# pcb-breakout-bt111.net
KiCad netlist of a schematic drawn in EAGLE
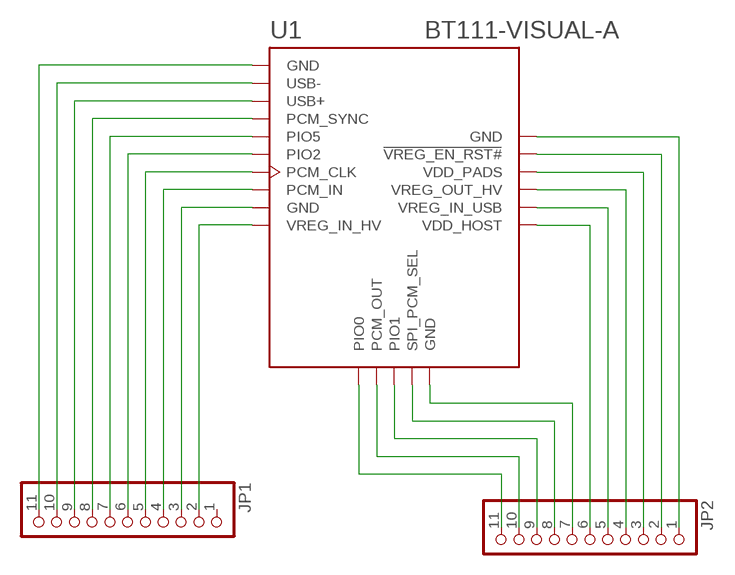
[diagram p0: schematic, sheet 1]

(export (version "E")
  (design (tool "Eeschema 10.0.6"))
  (components
    (comp (ref "JP1")
      (value "PINHD-1X11")
      (footprint "eagle-import:1X11")
      (libsource (lib "eagle-import") (part "PINHD-1X11"))
    )
    (comp (ref "JP2")
      (value "PINHD-1X11")
      (footprint "eagle-import:1X11")
      (libsource (lib "eagle-import") (part "PINHD-1X11"))
    )
    (comp (ref "U1")
      (value "BT111-VISUAL-A")
      (footprint "eagle-import:BT111-A")
      (libsource (lib "eagle-import") (part "BT111-VISUAL-A"))
    )
  )
  (nets
    (net (code "1") (name "Net-(JP1-Pad2)") (class "Default")
      (node (ref "JP1") (pin "2") (pinfunction "2_2") (pintype "passive"))
      (node (ref "U1") (pin "VREG_IN_HV") (pinfunction "VREG_IN_HV_VREG_IN_HV") (pintype "power_in"))
    )
    (net (code "2") (name "Net-(JP1-Pad3)") (class "Default")
      (node (ref "JP1") (pin "3") (pinfunction "3_3") (pintype "passive"))
      (node (ref "U1") (pin "GND@2") (pinfunction "GND_GND@2") (pintype "power_in"))
    )
    (net (code "3") (name "Net-(JP1-Pad4)") (class "Default")
      (node (ref "JP1") (pin "4") (pinfunction "4_4") (pintype "passive"))
      (node (ref "U1") (pin "PCM_IN") (pinfunction "PCM_IN_PCM_IN") (pintype "input"))
    )
    (net (code "4") (name "Net-(JP1-Pad5)") (class "Default")
      (node (ref "JP1") (pin "5") (pinfunction "5_5") (pintype "passive"))
      (node (ref "U1") (pin "PCM_CLK") (pinfunction "PCM_CLK_PCM_CLK") (pintype "bidirectional"))
    )
    (net (code "5") (name "Net-(JP1-Pad6)") (class "Default")
      (node (ref "JP1") (pin "6") (pinfunction "6_6") (pintype "passive"))
      (node (ref "U1") (pin "PIO2") (pinfunction "PIO2_PIO2") (pintype "bidirectional"))
    )
    (net (code "6") (name "Net-(JP1-Pad7)") (class "Default")
      (node (ref "JP1") (pin "7") (pinfunction "7_7") (pintype "passive"))
      (node (ref "U1") (pin "PIO5") (pinfunction "PIO5_PIO5") (pintype "bidirectional"))
    )
    (net (code "7") (name "Net-(JP1-Pad8)") (class "Default")
      (node (ref "JP1") (pin "8") (pinfunction "8_8") (pintype "passive"))
      (node (ref "U1") (pin "PCM_SYNC") (pinfunction "PCM_SYNC_PCM_SYNC") (pintype "bidirectional"))
    )
    (net (code "8") (name "Net-(JP1-Pad9)") (class "Default")
      (node (ref "JP1") (pin "9") (pinfunction "9_9") (pintype "passive"))
      (node (ref "U1") (pin "USB+") (pinfunction "USB+_USB+") (pintype "bidirectional"))
    )
    (net (code "9") (name "Net-(JP1-Pad10)") (class "Default")
      (node (ref "JP1") (pin "10") (pinfunction "10_10") (pintype "passive"))
      (node (ref "U1") (pin "USB-") (pinfunction "USB-_USB-") (pintype "bidirectional"))
    )
    (net (code "10") (name "Net-(JP1-Pad11)") (class "Default")
      (node (ref "JP1") (pin "11") (pinfunction "11_11") (pintype "passive"))
      (node (ref "U1") (pin "GND") (pinfunction "GND_GND") (pintype "power_in"))
    )
    (net (code "11") (name "Net-(JP2-Pad1)") (class "Default")
      (node (ref "JP2") (pin "1") (pinfunction "1_1") (pintype "passive"))
      (node (ref "U1") (pin "GND@4") (pinfunction "GND_GND@4") (pintype "power_in"))
    )
    (net (code "12") (name "Net-(JP2-Pad2)") (class "Default")
      (node (ref "JP2") (pin "2") (pinfunction "2_2") (pintype "passive"))
      (node (ref "U1") (pin "VREG_EN_RST#") (pinfunction "VREG_EN_RST#_VREG_EN_RST#") (pintype "input"))
    )
    (net (code "13") (name "Net-(JP2-Pad3)") (class "Default")
      (node (ref "JP2") (pin "3") (pinfunction "3_3") (pintype "passive"))
      (node (ref "U1") (pin "VDD_PADS") (pinfunction "VDD_PADS_VDD_PADS") (pintype "power_in"))
    )
    (net (code "14") (name "Net-(JP2-Pad4)") (class "Default")
      (node (ref "JP2") (pin "4") (pinfunction "4_4") (pintype "passive"))
      (node (ref "U1") (pin "VREG_OUT_HV") (pinfunction "VREG_OUT_HV_VREG_OUT_HV") (pintype "power_in"))
    )
    (net (code "15") (name "Net-(JP2-Pad5)") (class "Default")
      (node (ref "JP2") (pin "5") (pinfunction "5_5") (pintype "passive"))
      (node (ref "U1") (pin "VREG_IN_USB") (pinfunction "VREG_IN_USB_VREG_IN_USB") (pintype "power_in"))
    )
    (net (code "16") (name "Net-(JP2-Pad6)") (class "Default")
      (node (ref "JP2") (pin "6") (pinfunction "6_6") (pintype "passive"))
      (node (ref "U1") (pin "VDD_HOST") (pinfunction "VDD_HOST_VDD_HOST") (pintype "power_in"))
    )
    (net (code "17") (name "Net-(JP2-Pad7)") (class "Default")
      (node (ref "JP2") (pin "7") (pinfunction "7_7") (pintype "passive"))
      (node (ref "U1") (pin "GND@3") (pinfunction "GND_GND@3") (pintype "power_in"))
    )
    (net (code "18") (name "Net-(JP2-Pad8)") (class "Default")
      (node (ref "JP2") (pin "8") (pinfunction "8_8") (pintype "passive"))
      (node (ref "U1") (pin "SPI_PCM_SEL") (pinfunction "SPI_PCM_SEL_SPI_PCM_SEL") (pintype "input"))
    )
    (net (code "19") (name "Net-(JP2-Pad9)") (class "Default")
      (node (ref "JP2") (pin "9") (pinfunction "9_9") (pintype "passive"))
      (node (ref "U1") (pin "PIO1") (pinfunction "PIO1_PIO1") (pintype "bidirectional"))
    )
    (net (code "20") (name "Net-(JP2-Pad10)") (class "Default")
      (node (ref "JP2") (pin "10") (pinfunction "10_10") (pintype "passive"))
      (node (ref "U1") (pin "PCM_OUT") (pinfunction "PCM_OUT_PCM_OUT") (pintype "output"))
    )
    (net (code "21") (name "Net-(JP2-Pad11)") (class "Default")
      (node (ref "JP2") (pin "11") (pinfunction "11_11") (pintype "passive"))
      (node (ref "U1") (pin "PIO0") (pinfunction "PIO0_PIO0") (pintype "bidirectional"))
    )
    (net (code "22") (name "unconnected-(JP1-Pad1)") (class "Default")
      (node (ref "JP1") (pin "1") (pinfunction "1_1") (pintype "passive"))
    )
  )
)
